# Instrumental_Amplifire.net
KiCad netlist of a schematic drawn in Altium Designer
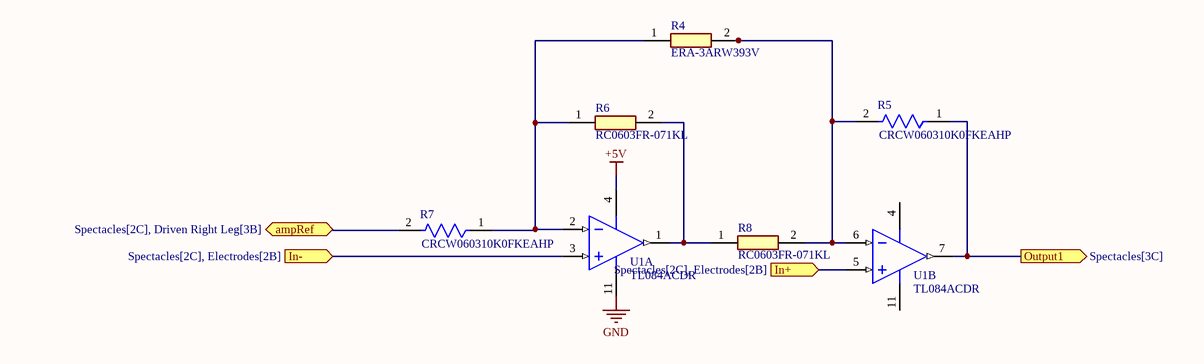
[diagram p0: Instrumental Amplifire.SchDoc]

(export (version "E")
  (design (tool "Eeschema 10.0.6"))
  (components
    (comp (ref "R4")
      (value "ERA-3ARW393V")
      (footprint "SamacSys:ERA3AEB101V")
      (description "Resistor")
      (fields (field (name "MOUSER PART NUMBER") "667-ERA-3ARW393V"))
      (libsource (lib "*") (part "ERA-3ARW393V"))
    )
    (comp (ref "R5")
      (value "CRCW060310K0FKEAHP")
      (footprint "FP-CRCW0603-HPe3-MFG")
      (description "RES SMD 10K OHM 1% 1/3W 0603")
      (fields (field (name "TOLERANCE") "1%"))
      (libsource (lib "Altium Content Vault") (part "1029c3af85768c4190bb7ad29bc67b5"))
    )
    (comp (ref "R6")
      (value "RC0603FR-071KL")
      (footprint "SamacSys:RESC1608X55N")
      (description "Resistor")
      (fields (field (name "MOUSER PART NUMBER") "603-RC0603FR-071KL"))
      (libsource (lib "*") (part "RC0603FR-071KL"))
    )
    (comp (ref "R7")
      (value "CRCW060310K0FKEAHP")
      (footprint "FP-CRCW0603-HPe3-MFG")
      (description "RES SMD 10K OHM 1% 1/3W 0603")
      (fields (field (name "TOLERANCE") "1%"))
      (libsource (lib "Altium Content Vault") (part "1029c3af85768c4190bb7ad29bc67b5"))
    )
    (comp (ref "R8")
      (value "RC0603FR-071KL")
      (footprint "SamacSys:RESC1608X55N")
      (description "Resistor")
      (fields (field (name "MOUSER PART NUMBER") "603-RC0603FR-071KL"))
      (libsource (lib "*") (part "RC0603FR-071KL"))
    )
    (comp (ref "U1")
      (value "TL084ACDR")
      (footprint "D0014A_N")
      (fields (field (name "MANUFACTURER") "Texas Instruments"))
      (libsource (lib "Altium Content Vault") (part "TI-TLXX4X_MC3403-X14"))
    )
  )
  (nets
    (net (code "1") (name "+5V") (class "Default")
      (node (ref "U1") (pin "4") (pinfunction "VCC+_4") (pintype "power_in"))
    )
    (net (code "2") (name "/In+") (class "Default")
      (node (ref "U1") (pin "5") (pinfunction "IN2+_5") (pintype "input"))
    )
    (net (code "3") (name "/In-") (class "Default")
      (node (ref "U1") (pin "3") (pinfunction "IN1+_3") (pintype "input"))
    )
    (net (code "4") (name "/Output1") (class "Default")
      (node (ref "R5") (pin "1") (pinfunction "1_1") (pintype "passive"))
      (node (ref "U1") (pin "7") (pinfunction "OUT2_7") (pintype "output"))
    )
    (net (code "5") (name "/ampRef") (class "Default")
      (node (ref "R7") (pin "2") (pinfunction "2_2") (pintype "passive"))
    )
    (net (code "6") (name "GND") (class "Default")
      (node (ref "U1") (pin "11") (pinfunction "VCC-_11") (pintype "power_in"))
    )
    (net (code "7") (name "Net-(U1A-IN1-)") (class "Default")
      (node (ref "R4") (pin "1") (pinfunction "1_1") (pintype "passive"))
      (node (ref "R6") (pin "1") (pinfunction "1_1") (pintype "passive"))
      (node (ref "R7") (pin "1") (pinfunction "1_1") (pintype "passive"))
      (node (ref "U1") (pin "2") (pinfunction "IN1-_2") (pintype "input"))
    )
    (net (code "8") (name "Net-(U1A-OUT1)") (class "Default")
      (node (ref "R6") (pin "2") (pinfunction "2_2") (pintype "passive"))
      (node (ref "R8") (pin "1") (pinfunction "1_1") (pintype "passive"))
      (node (ref "U1") (pin "1") (pinfunction "OUT1_1") (pintype "output"))
    )
    (net (code "9") (name "Net-(U1B-IN2-)") (class "Default")
      (node (ref "R4") (pin "2") (pinfunction "2_2") (pintype "passive"))
      (node (ref "R5") (pin "2") (pinfunction "2_2") (pintype "passive"))
      (node (ref "R8") (pin "2") (pinfunction "2_2") (pintype "passive"))
      (node (ref "U1") (pin "6") (pinfunction "IN2-_6") (pintype "input"))
    )
    (net (code "10") (name "unconnected-(U1B-VCC+-Pad4)") (class "Default")
      (node (ref "U1") (pin "4") (pinfunction "VCC+_4") (pintype "power_in"))
    )
    (net (code "11") (name "unconnected-(U1B-VCC--Pad11)") (class "Default")
      (node (ref "U1") (pin "11") (pinfunction "VCC-_11") (pintype "power_in"))
    )
  )
)
